# SheetArduinoUSB.net
KiCad netlist of a schematic drawn in Altium Designer
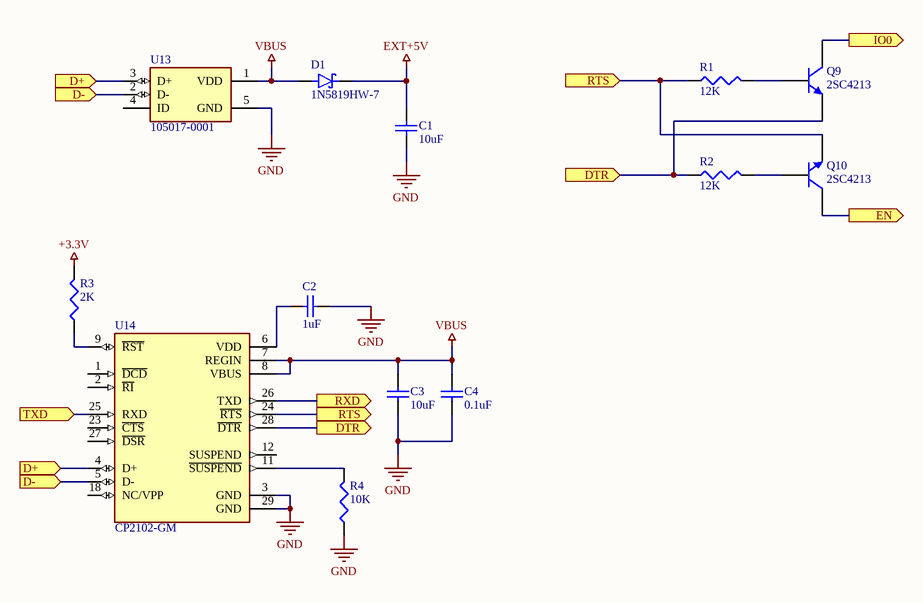
[diagram p0: SheetArduinoUSB.SchDoc]

(export (version "E")
  (design (tool "Eeschema 10.0.6"))
  (components
    (comp (ref "C1")
      (value "10uF")
      (footprint "C1206")
      (description "Capacitor (Semiconductor SIM Model)")
      (fields (field (name "PUBLISHER") "Altium Limited"))
      (libsource (lib "Miscellaneous Devices") (part "Cap Semi"))
    )
    (comp (ref "C2")
      (value "1uF")
      (footprint "1608[0603]")
      (description "Capacitor (Semiconductor SIM Model)")
      (fields (field (name "PUBLISHER") "Altium Limited"))
      (libsource (lib "Miscellaneous Devices") (part "Cap Semi"))
    )
    (comp (ref "C3")
      (value "10uF")
      (footprint "C1206")
      (description "Capacitor (Semiconductor SIM Model)")
      (fields (field (name "PUBLISHER") "Altium Limited"))
      (libsource (lib "Miscellaneous Devices") (part "Cap Semi"))
    )
    (comp (ref "C4")
      (value "0.1uF")
      (footprint "1608[0603]")
      (description "Capacitor (Semiconductor SIM Model)")
      (fields (field (name "PUBLISHER") "Altium Limited"))
      (libsource (lib "Miscellaneous Devices") (part "Cap Semi"))
    )
    (comp (ref "D1")
      (value "1N5819HW-7")
      (footprint "SOD3715X145N")
      (description "Diode Schottky 40 V 1A Surface Mount SOD-123")
      (fields (field (name "MF") "Diodes Inc."))
      (libsource (lib "1N5819HW-7") (part "1N5819HW-7"))
    )
    (comp (ref "Q9")
      (value "2SC4213")
      (footprint "SOT-23B_N")
      (description "NPN Bipolar Transistor")
      (fields (field (name "PUBLISHER") "Altium Limited"))
      (libsource (lib "Miscellaneous Devices") (part "QNPN"))
    )
    (comp (ref "Q10")
      (value "2SC4213")
      (footprint "SOT-23B_N")
      (description "NPN Bipolar Transistor")
      (fields (field (name "PUBLISHER") "Altium Limited"))
      (libsource (lib "Miscellaneous Devices") (part "QNPN"))
    )
    (comp (ref "R1")
      (value "12K")
      (footprint "J1-0603")
      (description "Resistor")
      (fields (field (name "PUBLISHER") "Altium Limited"))
      (libsource (lib "Miscellaneous Devices") (part "Res3"))
    )
    (comp (ref "R2")
      (value "12K")
      (footprint "J1-0603")
      (description "Resistor")
      (fields (field (name "PUBLISHER") "Altium Limited"))
      (libsource (lib "Miscellaneous Devices") (part "Res3"))
    )
    (comp (ref "R3")
      (value "2K")
      (footprint "J1-0603")
      (description "Resistor")
      (fields (field (name "PUBLISHER") "Altium Limited"))
      (libsource (lib "Miscellaneous Devices") (part "Res3"))
    )
    (comp (ref "R4")
      (value "10K")
      (footprint "J1-0603")
      (description "Resistor")
      (fields (field (name "PUBLISHER") "Altium Limited"))
      (libsource (lib "Miscellaneous Devices") (part "Res3"))
    )
    (comp (ref "U13")
      (value "105017-0001")
      (footprint "MOLEX_105017-0001")
      (description "USB - micro B USB 2.0 Receptacle Connector 5 Position Surface Mount, Right Angle; Through Hole")
      (fields (field (name "MF") "Molex"))
      (libsource (lib "105017-0001") (part "105017-0001"))
    )
    (comp (ref "U14")
      (value "CP2102-GM")
      (footprint "QFN50P500X500X100-29N")
      (description "USB Bridge, USB to UART USB 2.0 UART Interface 28-QFN _5x5_")
      (fields (field (name "MF") "Silicon Labs"))
      (libsource (lib "CP2102-GM") (part "CP2102-GM"))
    )
  )
  (nets
    (net (code "1") (name "+3.3V") (class "Default")
      (node (ref "R3") (pin "2") (pinfunction "2_2") (pintype "passive"))
    )
    (net (code "2") (name "/D+") (class "Default")
      (node (ref "U13") (pin "3") (pinfunction "D+_3") (pintype "bidirectional"))
      (node (ref "U14") (pin "4") (pinfunction "D+_4") (pintype "bidirectional"))
    )
    (net (code "3") (name "/D-") (class "Default")
      (node (ref "U13") (pin "2") (pinfunction "D-_2") (pintype "bidirectional"))
      (node (ref "U14") (pin "5") (pinfunction "D-_5") (pintype "bidirectional"))
    )
    (net (code "4") (name "/DTR") (class "Default")
      (node (ref "Q9") (pin "3") (pinfunction "E_3") (pintype "passive"))
      (node (ref "R2") (pin "1") (pinfunction "1_1") (pintype "passive"))
      (node (ref "U14") (pin "28") (pinfunction "~{DTR}_28") (pintype "output"))
    )
    (net (code "5") (name "/EN") (class "Default")
      (node (ref "Q10") (pin "1") (pinfunction "C_1") (pintype "passive"))
    )
    (net (code "6") (name "/IO0") (class "Default")
      (node (ref "Q9") (pin "1") (pinfunction "C_1") (pintype "passive"))
    )
    (net (code "7") (name "/RTS") (class "Default")
      (node (ref "Q10") (pin "3") (pinfunction "E_3") (pintype "passive"))
      (node (ref "R1") (pin "1") (pinfunction "1_1") (pintype "passive"))
      (node (ref "U14") (pin "24") (pinfunction "~{RTS}_24") (pintype "output"))
    )
    (net (code "8") (name "/RXD") (class "Default")
      (node (ref "U14") (pin "26") (pinfunction "TXD_26") (pintype "output"))
    )
    (net (code "9") (name "/TXD") (class "Default")
      (node (ref "U14") (pin "25") (pinfunction "RXD_25") (pintype "input"))
    )
    (net (code "10") (name "EXT+5V") (class "Default")
      (node (ref "C1") (pin "2") (pinfunction "2_2") (pintype "passive"))
      (node (ref "D1") (pin "C") (pinfunction "K_C") (pintype "passive"))
    )
    (net (code "11") (name "GND") (class "Default")
      (node (ref "C1") (pin "1") (pinfunction "1_1") (pintype "passive"))
      (node (ref "C2") (pin "1") (pinfunction "1_1") (pintype "passive"))
      (node (ref "C3") (pin "1") (pinfunction "1_1") (pintype "passive"))
      (node (ref "C4") (pin "1") (pinfunction "1_1") (pintype "passive"))
      (node (ref "R4") (pin "1") (pinfunction "1_1") (pintype "passive"))
      (node (ref "U13") (pin "5") (pinfunction "GND_5") (pintype "power_in"))
      (node (ref "U14") (pin "29") (pinfunction "GND_29") (pintype "power_in"))
      (node (ref "U14") (pin "3") (pinfunction "GND_3") (pintype "power_in"))
    )
    (net (code "12") (name "Net-(Q9-B)") (class "Default")
      (node (ref "Q9") (pin "2") (pinfunction "B_2") (pintype "passive"))
      (node (ref "R1") (pin "2") (pinfunction "2_2") (pintype "passive"))
    )
    (net (code "13") (name "Net-(Q10-B)") (class "Default")
      (node (ref "Q10") (pin "2") (pinfunction "B_2") (pintype "passive"))
      (node (ref "R2") (pin "2") (pinfunction "2_2") (pintype "passive"))
    )
    (net (code "14") (name "Net-(U14-VDD)") (class "Default")
      (node (ref "C2") (pin "2") (pinfunction "2_2") (pintype "passive"))
      (node (ref "U14") (pin "6") (pinfunction "VDD_6") (pintype "power_in"))
    )
    (net (code "15") (name "Net-(U14-~{RST})") (class "Default")
      (node (ref "R3") (pin "1") (pinfunction "1_1") (pintype "passive"))
      (node (ref "U14") (pin "9") (pinfunction "~{RST}_9") (pintype "bidirectional"))
    )
    (net (code "16") (name "Net-(U14-~{SUSPEND})") (class "Default")
      (node (ref "R4") (pin "2") (pinfunction "2_2") (pintype "passive"))
      (node (ref "U14") (pin "11") (pinfunction "~{SUSPEND}_11") (pintype "output"))
    )
    (net (code "17") (name "VBUS") (class "Default")
      (node (ref "C3") (pin "2") (pinfunction "2_2") (pintype "passive"))
      (node (ref "C4") (pin "2") (pinfunction "2_2") (pintype "passive"))
      (node (ref "D1") (pin "A") (pinfunction "A_A") (pintype "passive"))
      (node (ref "U13") (pin "1") (pinfunction "VDD_1") (pintype "power_in"))
      (node (ref "U14") (pin "7") (pinfunction "REGIN_7") (pintype "power_in"))
      (node (ref "U14") (pin "8") (pinfunction "VBUS_8") (pintype "power_in"))
    )
    (net (code "18") (name "unconnected-(U13-ID-Pad4)") (class "Default")
      (node (ref "U13") (pin "4") (pinfunction "ID_4") (pintype "passive"))
    )
    (net (code "19") (name "unconnected-(U14-NC{slash}VPP-Pad18)") (class "Default")
      (node (ref "U14") (pin "18") (pinfunction "NC/VPP_18") (pintype "bidirectional"))
    )
    (net (code "20") (name "unconnected-(U14-SUSPEND-Pad12)") (class "Default")
      (node (ref "U14") (pin "12") (pinfunction "SUSPEND_12") (pintype "output"))
    )
    (net (code "21") (name "unconnected-(U14-~{CTS}-Pad23)") (class "Default")
      (node (ref "U14") (pin "23") (pinfunction "~{CTS}_23") (pintype "input"))
    )
    (net (code "22") (name "unconnected-(U14-~{DCD}-Pad1)") (class "Default")
      (node (ref "U14") (pin "1") (pinfunction "~{DCD}_1") (pintype "input"))
    )
    (net (code "23") (name "unconnected-(U14-~{DSR}-Pad27)") (class "Default")
      (node (ref "U14") (pin "27") (pinfunction "~{DSR}_27") (pintype "input"))
    )
    (net (code "24") (name "unconnected-(U14-~{RI}-Pad2)") (class "Default")
      (node (ref "U14") (pin "2") (pinfunction "~{RI}_2") (pintype "input"))
    )
  )
)
